# Amp.net
KiCad netlist of a schematic drawn in Altium Designer
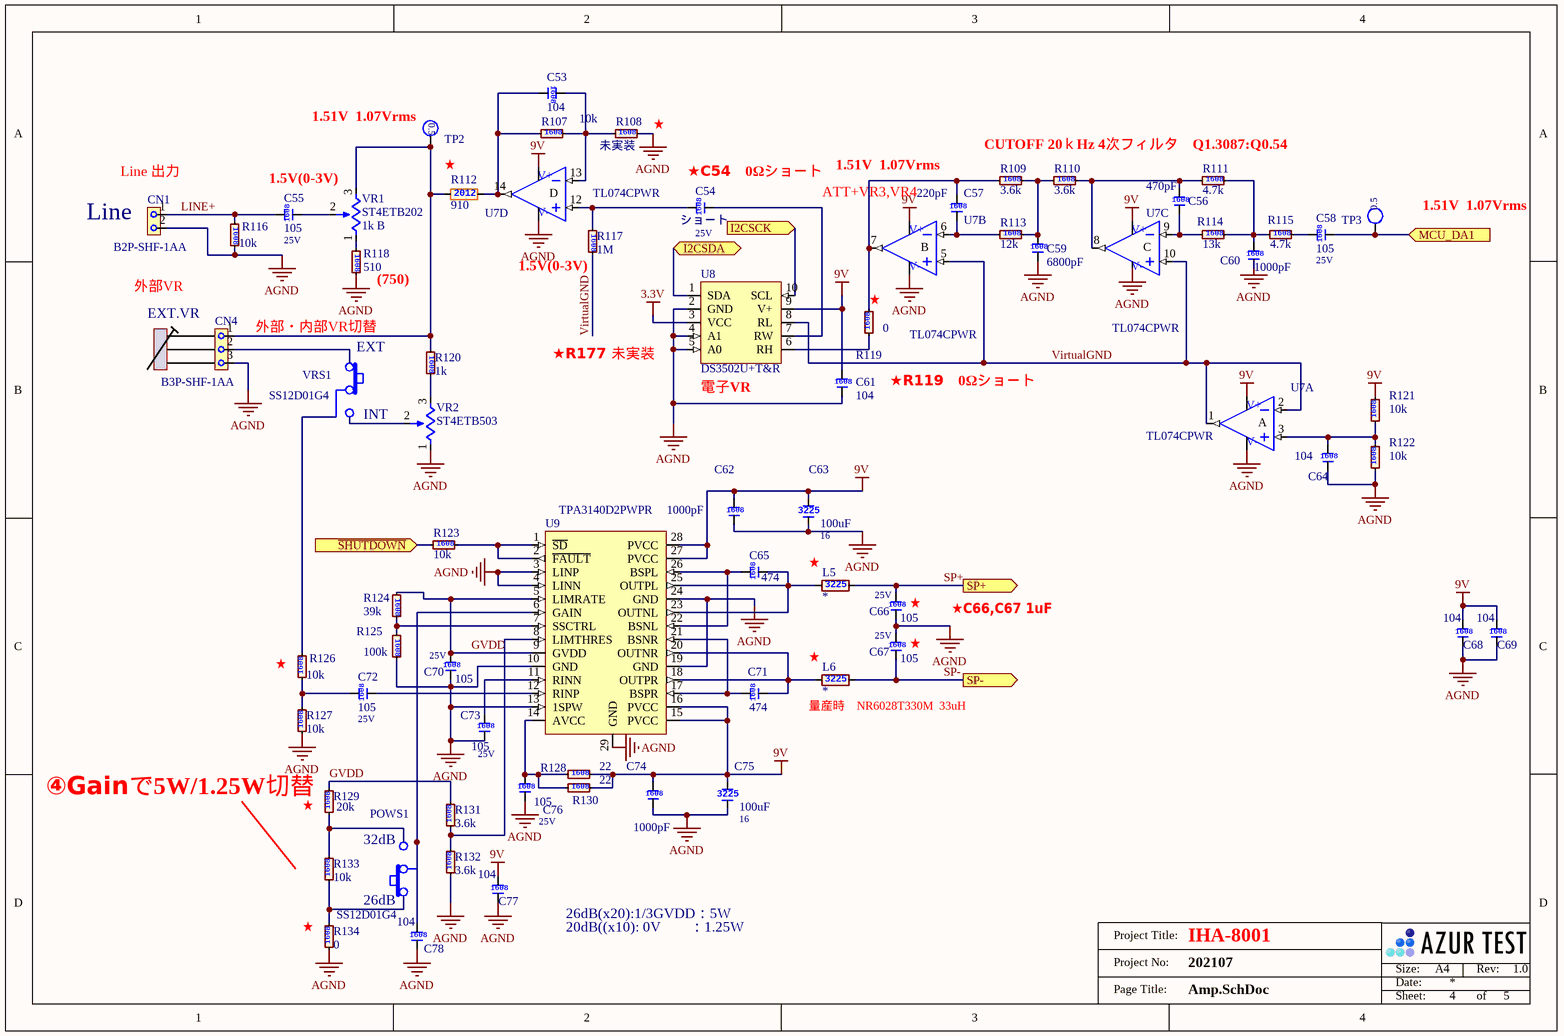
[diagram p0: Amp.SchDoc]

(export (version "E")
  (design (tool "Eeschema 10.0.6"))
  (components
    (comp (ref "C53")
      (value "CGA3E2X7R1H104K080AA")
      (footprint "C1608")
      (description "セラコン1608サイズ")
      (fields (field (name "TAG") "104") (field (name "VOLTAGE") "50V"))
      (libsource (lib "Audio") (part "C1608"))
    )
    (comp (ref "C54")
      (value "TMK107BJ105MA-T")
      (footprint "C1608")
      (description "セラコン1608サイズ")
      (fields (field (name "TAG") "ショート") (field (name "VOLTAGE") "25V"))
      (libsource (lib "Audio") (part "C1608"))
    )
    (comp (ref "C55")
      (value "TMK107BJ105MA-T")
      (footprint "C1608")
      (description "セラコン1608サイズ")
      (fields (field (name "TAG") "105") (field (name "VOLTAGE") "25V"))
      (libsource (lib "Audio") (part "C1608"))
    )
    (comp (ref "C56")
      (value "GCM1885C2A471JA16D")
      (footprint "C1608")
      (description "セラコン1608サイズ")
      (fields (field (name "TAG") "470pF") (field (name "VOLTAGE") "100V"))
      (libsource (lib "Audio") (part "C1608"))
    )
    (comp (ref "C57")
      (value "GCM1885C2A221JA16D")
      (footprint "C1608")
      (description "セラコン1608サイズ")
      (fields (field (name "TAG") "220pF") (field (name "VOLTAGE") "100V"))
      (libsource (lib "Audio") (part "C1608"))
    )
    (comp (ref "C58")
      (value "TMK107BJ105MA-T")
      (footprint "C1608")
      (description "セラコン1608サイズ")
      (fields (field (name "TAG") "105") (field (name "VOLTAGE") "25V"))
      (libsource (lib "Audio") (part "C1608"))
    )
    (comp (ref "C59")
      (value "GCM1885C2A682JA16D")
      (footprint "C1608")
      (description "セラコン1608サイズ")
      (fields (field (name "TAG") "6800pF") (field (name "VOLTAGE") "100V"))
      (libsource (lib "Audio") (part "C1608"))
    )
    (comp (ref "C60")
      (value "GCM1885C2A102JA16D")
      (footprint "C1608")
      (description "セラコン1608サイズ")
      (fields (field (name "TAG") "1000pF") (field (name "VOLTAGE") "100V"))
      (libsource (lib "Audio") (part "C1608"))
    )
    (comp (ref "C61")
      (value "CGA3E2X7R1H104K080AA")
      (footprint "C1608")
      (description "セラコン1608サイズ")
      (fields (field (name "TAG") "104") (field (name "VOLTAGE") "50V"))
      (libsource (lib "Audio") (part "C1608"))
    )
    (comp (ref "C62")
      (value "GCM1885C2A102JA16D")
      (footprint "C1608")
      (description "セラコン1608サイズ")
      (fields (field (name "TAG") "1000pF") (field (name "VOLTAGE") "100V"))
      (libsource (lib "Audio") (part "C1608"))
    )
    (comp (ref "C63")
      (value "EMK325ABJ107MM-T")
      (footprint "C3225")
      (description "セラコン3225サイズ")
      (fields (field (name "TAG") "100uF") (field (name "VOLTAGE") "16"))
      (libsource (lib "Audio") (part "C3225"))
    )
    (comp (ref "C64")
      (value "CGA3E2X7R1H104K080AA")
      (footprint "C1608")
      (description "セラコン1608サイズ")
      (fields (field (name "TAG") "104") (field (name "VOLTAGE") "50V"))
      (libsource (lib "Audio") (part "C1608"))
    )
    (comp (ref "C65")
      (value "UMK107B7474KA-TR")
      (footprint "C1608")
      (description "セラコン1608サイズ")
      (fields (field (name "TAG") "474") (field (name "VOLTAGE") "25V"))
      (libsource (lib "Audio") (part "C1608"))
    )
    (comp (ref "C66")
      (value "TMK107BJ105MA-T")
      (footprint "C1608")
      (description "セラコン1608サイズ")
      (fields (field (name "TAG") "105") (field (name "VOLTAGE") "25V"))
      (libsource (lib "Audio") (part "C1608"))
    )
    (comp (ref "C67")
      (value "TMK107BJ105MA-T")
      (footprint "C1608")
      (description "セラコン1608サイズ")
      (fields (field (name "TAG") "105") (field (name "VOLTAGE") "25V"))
      (libsource (lib "Audio") (part "C1608"))
    )
    (comp (ref "C68")
      (value "CGA3E2X7R1H104K080AA")
      (footprint "C1608")
      (description "セラコン1608サイズ")
      (fields (field (name "TAG") "104") (field (name "VOLTAGE") "50V"))
      (libsource (lib "Audio") (part "C1608"))
    )
    (comp (ref "C69")
      (value "CGA3E2X7R1H104K080AA")
      (footprint "C1608")
      (description "セラコン1608サイズ")
      (fields (field (name "TAG") "104") (field (name "VOLTAGE") "50V"))
      (libsource (lib "Audio") (part "C1608"))
    )
    (comp (ref "C70")
      (value "TMK107BJ105MA-T")
      (footprint "C1608")
      (description "セラコン1608サイズ")
      (fields (field (name "TAG") "105") (field (name "VOLTAGE") "25V"))
      (libsource (lib "Audio") (part "C1608"))
    )
    (comp (ref "C71")
      (value "UMK107B7474KA-TR")
      (footprint "C1608")
      (description "セラコン1608サイズ")
      (fields (field (name "TAG") "474") (field (name "VOLTAGE") "25V"))
      (libsource (lib "Audio") (part "C1608"))
    )
    (comp (ref "C72")
      (value "TMK107BJ105MA-T")
      (footprint "C1608")
      (description "セラコン1608サイズ")
      (fields (field (name "TAG") "105") (field (name "VOLTAGE") "25V"))
      (libsource (lib "Audio") (part "C1608"))
    )
    (comp (ref "C73")
      (value "TMK107BJ105MA-T")
      (footprint "C1608")
      (description "セラコン1608サイズ")
      (fields (field (name "TAG") "105") (field (name "VOLTAGE") "25V"))
      (libsource (lib "Audio") (part "C1608"))
    )
    (comp (ref "C74")
      (value "GCM1885C2A102JA16D")
      (footprint "C1608")
      (description "セラコン1608サイズ")
      (fields (field (name "TAG") "1000pF") (field (name "VOLTAGE") "100V"))
      (libsource (lib "Audio") (part "C1608"))
    )
    (comp (ref "C75")
      (value "EMK325ABJ107MM-T")
      (footprint "C3225")
      (description "セラコン3225サイズ")
      (fields (field (name "TAG") "100uF") (field (name "VOLTAGE") "16"))
      (libsource (lib "Audio") (part "C3225"))
    )
    (comp (ref "C76")
      (value "TMK107BJ105MA-T")
      (footprint "C1608")
      (description "セラコン1608サイズ")
      (fields (field (name "TAG") "105") (field (name "VOLTAGE") "25V"))
      (libsource (lib "Audio") (part "C1608"))
    )
    (comp (ref "C77")
      (value "CGA3E2X7R1H104K080AA")
      (footprint "C1608")
      (description "セラコン1608サイズ")
      (fields (field (name "TAG") "104") (field (name "VOLTAGE") "50V"))
      (libsource (lib "Audio") (part "C1608"))
    )
    (comp (ref "C78")
      (value "CGA3E2X7R1H104K080AA")
      (footprint "C1608")
      (description "セラコン1608サイズ")
      (fields (field (name "TAG") "104") (field (name "VOLTAGE") "50V"))
      (libsource (lib "Audio") (part "C1608"))
    )
    (comp (ref "CN1")
      (value "B2P-SHF-1AA")
      (footprint "B2P-SHF-1AA")
      (description "雄,ストレート,1列2ピン")
      (libsource (lib "Audio Prj_1") (part "B2P-SHF-1AA"))
    )
    (comp (ref "CN4")
      (value "B3P-SHF-1AA")
      (footprint "B3P-SHF-1AA")
      (description "雄,ストレート,1列3ピン")
      (libsource (lib "Audio") (part "B3P-SHF-1AA"))
    )
    (comp (ref "L5")
      (value "TF3225")
      (footprint "R3225")
      (description "厚膜チップ抵抗3225サイズ")
      (fields (field (name "TAG") "*"))
      (libsource (lib "Audio Prj") (part "TF3225"))
    )
    (comp (ref "L6")
      (value "TF3225")
      (footprint "R3225")
      (description "厚膜チップ抵抗3225サイズ")
      (fields (field (name "TAG") "*"))
      (libsource (lib "Audio Prj") (part "TF3225"))
    )
    (comp (ref "POWS1")
      (value "SS12D01G4")
      (footprint "SS12D01G4")
      (description "SPDTスライドスイッチ")
      (libsource (lib "Audio Prj") (part "SS12D01G4"))
    )
    (comp (ref "R107")
      (value "ERJ-PA3F1002V")
      (footprint "R1608")
      (description "厚膜チップ抵抗1608サイズ")
      (fields (field (name "TAG") "10k"))
      (libsource (lib "") (part "TF1608_1"))
    )
    (comp (ref "R108")
      (value "ERJ-PA3F1002V")
      (footprint "R1608")
      (description "厚膜チップ抵抗1608サイズ")
      (fields (field (name "TAG") "未実装"))
      (libsource (lib "") (part "TF1608_1"))
    )
    (comp (ref "R109")
      (value "ERJ-PA3F3601V")
      (footprint "R1608")
      (description "厚膜チップ抵抗1608サイズ")
      (fields (field (name "TAG") "3.6k"))
      (libsource (lib "") (part "TF1608_1"))
    )
    (comp (ref "R110")
      (value "ERJ-PA3F3601V")
      (footprint "R1608")
      (description "厚膜チップ抵抗1608サイズ")
      (fields (field (name "TAG") "3.6k"))
      (libsource (lib "") (part "TF1608_1"))
    )
    (comp (ref "R111")
      (value "ERJ-PA3F4701V")
      (footprint "R1608")
      (description "厚膜チップ抵抗1608サイズ")
      (fields (field (name "TAG") "4.7k"))
      (libsource (lib "") (part "TF1608_1"))
    )
    (comp (ref "R112")
      (value "ERJ-P08J911V")
      (footprint "R2012")
      (description "薄膜チップ抵抗2012サイズ")
      (fields (field (name "TAG") "910"))
      (libsource (lib "Audio") (part "MF2012"))
    )
    (comp (ref "R113")
      (value "ERJ-PA3F1201V")
      (footprint "R1608")
      (description "厚膜チップ抵抗1608サイズ")
      (fields (field (name "TAG") "12k"))
      (libsource (lib "") (part "TF1608_1"))
    )
    (comp (ref "R114")
      (value "ERJ-PA3F1302V")
      (footprint "R1608")
      (description "厚膜チップ抵抗1608サイズ")
      (fields (field (name "TAG") "13k"))
      (libsource (lib "") (part "TF1608_1"))
    )
    (comp (ref "R115")
      (value "ERJ-PA3F4701V")
      (footprint "R1608")
      (description "厚膜チップ抵抗1608サイズ")
      (fields (field (name "TAG") "4.7k"))
      (libsource (lib "") (part "TF1608_1"))
    )
    (comp (ref "R116")
      (value "ERJ-PA3F1002V")
      (footprint "R1608")
      (description "厚膜チップ抵抗1608サイズ")
      (fields (field (name "TAG") "10k"))
      (libsource (lib "Schlib1") (part "TF1608"))
    )
    (comp (ref "R117")
      (value "ERJ-PA3F1004V")
      (footprint "R1608")
      (description "厚膜チップ抵抗1608サイズ")
      (fields (field (name "TAG") "1M"))
      (libsource (lib "Schlib1") (part "TF1608"))
    )
    (comp (ref "R118")
      (value "ERJ-PA3F5100V")
      (footprint "R1608")
      (description "厚膜チップ抵抗1608サイズ")
      (fields (field (name "TAG") "510"))
      (libsource (lib "Schlib1") (part "TF1608"))
    )
    (comp (ref "R119")
      (value "ERJ-S030R00V")
      (footprint "R1608")
      (description "厚膜チップ抵抗1608サイズ")
      (fields (field (name "TAG") "0"))
      (libsource (lib "") (part "TF1608_2"))
    )
    (comp (ref "R120")
      (value "ERJ-PA3F1001V")
      (footprint "R1608")
      (description "厚膜チップ抵抗1608サイズ")
      (fields (field (name "TAG") "1k"))
      (libsource (lib "Schlib1") (part "TF1608"))
    )
    (comp (ref "R121")
      (value "ERJ-PA3F1002V")
      (footprint "R1608")
      (description "厚膜チップ抵抗1608サイズ")
      (fields (field (name "TAG") "10k"))
      (libsource (lib "") (part "TF1608_2"))
    )
    (comp (ref "R122")
      (value "ERJ-PA3F1002V")
      (footprint "R1608")
      (description "厚膜チップ抵抗1608サイズ")
      (fields (field (name "TAG") "10k"))
      (libsource (lib "") (part "TF1608_2"))
    )
    (comp (ref "R123")
      (value "ERJ-PA3F1002V")
      (footprint "R1608")
      (description "厚膜チップ抵抗1608サイズ")
      (fields (field (name "TAG") "10k"))
      (libsource (lib "") (part "TF1608_1"))
    )
    (comp (ref "R124")
      (value "ERJ-PA3F3902V")
      (footprint "R1608")
      (description "厚膜チップ抵抗1608サイズ")
      (fields (field (name "TAG") "39k"))
      (libsource (lib "Schlib1") (part "TF1608"))
    )
    (comp (ref "R125")
      (value "ERJ-PA3F3902V")
      (footprint "R1608")
      (description "厚膜チップ抵抗1608サイズ")
      (fields (field (name "TAG") "100k"))
      (libsource (lib "Schlib1") (part "TF1608"))
    )
    (comp (ref "R126")
      (value "ERJ-PA3F1002V")
      (footprint "R1608")
      (description "厚膜チップ抵抗1608サイズ")
      (fields (field (name "TAG") "10k"))
      (libsource (lib "") (part "TF1608_2"))
    )
    (comp (ref "R127")
      (value "ERJ-PA3F1002V")
      (footprint "R1608")
      (description "厚膜チップ抵抗1608サイズ")
      (fields (field (name "TAG") "10k"))
      (libsource (lib "") (part "TF1608_2"))
    )
    (comp (ref "R128")
      (value "ERJ-PA3F22R0V")
      (footprint "R1608")
      (description "厚膜チップ抵抗1608サイズ")
      (fields (field (name "TAG") "22"))
      (libsource (lib "") (part "TF1608_1"))
    )
    (comp (ref "R129")
      (value "ERJ-PA3F2002V")
      (footprint "R1608")
      (description "厚膜チップ抵抗1608サイズ")
      (fields (field (name "TAG") "20k"))
      (libsource (lib "") (part "TF1608_2"))
    )
    (comp (ref "R130")
      (value "ERJ-PA3F22R0V")
      (footprint "R1608")
      (description "厚膜チップ抵抗1608サイズ")
      (fields (field (name "TAG") "22"))
      (libsource (lib "") (part "TF1608_1"))
    )
    (comp (ref "R131")
      (value "ERJ-PA3F3601V")
      (footprint "R1608")
      (description "厚膜チップ抵抗1608サイズ")
      (fields (field (name "TAG") "3.6k"))
      (libsource (lib "") (part "TF1608_2"))
    )
    (comp (ref "R132")
      (value "ERJ-PA3F3601V")
      (footprint "R1608")
      (description "厚膜チップ抵抗1608サイズ")
      (fields (field (name "TAG") "3.6k"))
      (libsource (lib "") (part "TF1608_2"))
    )
    (comp (ref "R133")
      (value "ERJ-PA3F1002V")
      (footprint "R1608")
      (description "厚膜チップ抵抗1608サイズ")
      (fields (field (name "TAG") "10k"))
      (libsource (lib "") (part "TF1608_2"))
    )
    (comp (ref "R134")
      (value "ERJ-S030R00V")
      (footprint "R1608")
      (description "厚膜チップ抵抗1608サイズ")
      (fields (field (name "TAG") "0"))
      (libsource (lib "") (part "TF1608_2"))
    )
    (comp (ref "TP2")
      (value "TP0.5mm")
      (footprint "TP0.5mm")
      (description "Test-Point 0.5mm")
      (libsource (lib "Audio") (part "TP0.5mm"))
    )
    (comp (ref "TP3")
      (value "TP0.5mm")
      (footprint "TP0.5mm")
      (description "Test-Point 0.5mm")
      (libsource (lib "Audio") (part "TP0.5mm"))
    )
    (comp (ref "U7")
      (value "TL074CPWR")
      (footprint "TSSOP14")
      (description "IC OPAMP JFET 4 CIRCUIT 14TSSOP")
      (libsource (lib "Audio Prj") (part "TL084CPT"))
    )
    (comp (ref "U8")
      (value "DS3502U+T&R")
      (footprint "MSOP10")
      (description "IC DGTL POT 10KOHM 128TAP 10UMAX")
      (libsource (lib "Audio Prj") (part "DS3502U+T&R"))
    )
    (comp (ref "U9")
      (value "TPA3140D2PWPR")
      (footprint "TSSOP28")
      (description "IC AMP CLASS D STER 10W 28HTSSOP")
      (libsource (lib "Audio Prj") (part "TPA3140D2PWPR"))
    )
    (comp (ref "VR1")
      (value "ST4ETB202")
      (footprint "ST4ETB202")
      (description "CERMET TRIMMER  Top adjustmet")
      (fields (field (name "TAG") "1k B"))
      (libsource (lib "Audio") (part "ST-32EA**"))
    )
    (comp (ref "VR2")
      (value "ST4ETB503")
      (footprint "ST4ETB202")
      (description "CERMET TRIMMER  Top adjustmet")
      (libsource (lib "Audio") (part "ST-32EA**"))
    )
    (comp (ref "VRS1")
      (value "SS12D01G4")
      (footprint "SS12D01G4")
      (description "SPDTスライドスイッチ")
      (libsource (lib "Audio Prj") (part "SS12D01G4"))
    )
  )
  (nets
    (net (code "1") (name "/GVDD") (class "Default")
      (node (ref "C70") (pin "2") (pinfunction "2_2") (pintype "passive"))
      (node (ref "R124") (pin "1") (pinfunction "1_1") (pintype "passive"))
      (node (ref "R129") (pin "2") (pinfunction "2_2") (pintype "passive"))
      (node (ref "R131") (pin "2") (pinfunction "2_2") (pintype "passive"))
      (node (ref "U9") (pin "5") (pinfunction "LIMRATE_5") (pintype "input"))
      (node (ref "U9") (pin "9") (pinfunction "GVDD_9") (pintype "power_in"))
    )
    (net (code "2") (name "/I2CSCK") (class "Default")
      (node (ref "U8") (pin "10") (pinfunction "SCL_10") (pintype "input"))
    )
    (net (code "3") (name "/I2CSDA") (class "Default")
      (node (ref "U8") (pin "1") (pinfunction "SDA_1") (pintype "bidirectional"))
    )
    (net (code "4") (name "/LINE+") (class "Default")
      (node (ref "C55") (pin "2") (pinfunction "2_2") (pintype "passive"))
      (node (ref "CN1") (pin "1") (pinfunction "1_1") (pintype "passive"))
      (node (ref "R116") (pin "1") (pinfunction "1_1") (pintype "passive"))
    )
    (net (code "5") (name "/MCU_DA1") (class "Default")
      (node (ref "C58") (pin "1") (pinfunction "1_1") (pintype "passive"))
      (node (ref "TP3") (pin "1") (pinfunction "1_1") (pintype "passive"))
    )
    (net (code "6") (name "/SP+") (class "Default")
      (node (ref "C66") (pin "2") (pinfunction "2_2") (pintype "passive"))
      (node (ref "L5") (pin "2") (pinfunction "2_2") (pintype "passive"))
    )
    (net (code "7") (name "/SP-") (class "Default")
      (node (ref "C67") (pin "1") (pinfunction "1_1") (pintype "passive"))
      (node (ref "L6") (pin "2") (pinfunction "2_2") (pintype "passive"))
    )
    (net (code "8") (name "/VirtualGND") (class "Default")
      (node (ref "R117") (pin "2") (pinfunction "2_2") (pintype "passive"))
      (node (ref "U7") (pin "1") (pinfunction "OUT_1") (pintype "output"))
      (node (ref "U7") (pin "10") (pinfunction "IN+_10") (pintype "input"))
      (node (ref "U7") (pin "2") (pinfunction "IN-_2") (pintype "input"))
      (node (ref "U7") (pin "5") (pinfunction "IN+_5") (pintype "input"))
      (node (ref "U8") (pin "8") (pinfunction "RL_8") (pintype "passive"))
    )
    (net (code "9") (name "/~{SHUTDOWN}") (class "Default")
      (node (ref "R123") (pin "1") (pinfunction "1_1") (pintype "passive"))
    )
    (net (code "10") (name "3.3V") (class "Default")
      (node (ref "U8") (pin "3") (pinfunction "VCC_3") (pintype "power_in"))
    )
    (net (code "11") (name "9V") (class "Default")
      (node (ref "C61") (pin "2") (pinfunction "2_2") (pintype "passive"))
      (node (ref "C62") (pin "2") (pinfunction "2_2") (pintype "passive"))
      (node (ref "C63") (pin "2") (pinfunction "2_2") (pintype "passive"))
      (node (ref "C68") (pin "2") (pinfunction "2_2") (pintype "passive"))
      (node (ref "C69") (pin "2") (pinfunction "2_2") (pintype "passive"))
      (node (ref "C74") (pin "2") (pinfunction "2_2") (pintype "passive"))
      (node (ref "C75") (pin "2") (pinfunction "2_2") (pintype "passive"))
      (node (ref "C77") (pin "2") (pinfunction "2_2") (pintype "passive"))
      (node (ref "R121") (pin "2") (pinfunction "2_2") (pintype "passive"))
      (node (ref "R128") (pin "2") (pinfunction "2_2") (pintype "passive"))
      (node (ref "R130") (pin "2") (pinfunction "2_2") (pintype "passive"))
      (node (ref "U7") (pin "4") (pinfunction "V+_4") (pintype "power_in"))
      (node (ref "U8") (pin "9") (pinfunction "V+_9") (pintype "power_in"))
      (node (ref "U9") (pin "15") (pinfunction "PVCC_15") (pintype "power_in"))
      (node (ref "U9") (pin "16") (pinfunction "PVCC_16") (pintype "power_in"))
      (node (ref "U9") (pin "27") (pinfunction "PVCC_27") (pintype "power_in"))
      (node (ref "U9") (pin "28") (pinfunction "PVCC_28") (pintype "power_in"))
    )
    (net (code "12") (name "AGND") (class "Default")
      (node (ref "C59") (pin "1") (pinfunction "1_1") (pintype "passive"))
      (node (ref "C60") (pin "1") (pinfunction "1_1") (pintype "passive"))
      (node (ref "C61") (pin "1") (pinfunction "1_1") (pintype "passive"))
      (node (ref "C62") (pin "1") (pinfunction "1_1") (pintype "passive"))
      (node (ref "C63") (pin "1") (pinfunction "1_1") (pintype "passive"))
      (node (ref "C64") (pin "1") (pinfunction "1_1") (pintype "passive"))
      (node (ref "C66") (pin "1") (pinfunction "1_1") (pintype "passive"))
      (node (ref "C67") (pin "2") (pinfunction "2_2") (pintype "passive"))
      (node (ref "C68") (pin "1") (pinfunction "1_1") (pintype "passive"))
      (node (ref "C69") (pin "1") (pinfunction "1_1") (pintype "passive"))
      (node (ref "C70") (pin "1") (pinfunction "1_1") (pintype "passive"))
      (node (ref "C73") (pin "1") (pinfunction "1_1") (pintype "passive"))
      (node (ref "C74") (pin "1") (pinfunction "1_1") (pintype "passive"))
      (node (ref "C75") (pin "1") (pinfunction "1_1") (pintype "passive"))
      (node (ref "C76") (pin "1") (pinfunction "1_1") (pintype "passive"))
      (node (ref "C77") (pin "1") (pinfunction "1_1") (pintype "passive"))
      (node (ref "C78") (pin "1") (pinfunction "1_1") (pintype "passive"))
      (node (ref "CN1") (pin "2") (pinfunction "2_2") (pintype "passive"))
      (node (ref "CN4") (pin "3") (pinfunction "3_3") (pintype "passive"))
      (node (ref "R108") (pin "2") (pinfunction "2_2") (pintype "passive"))
      (node (ref "R116") (pin "2") (pinfunction "2_2") (pintype "passive"))
      (node (ref "R118") (pin "2") (pinfunction "2_2") (pintype "passive"))
      (node (ref "R122") (pin "1") (pinfunction "1_1") (pintype "passive"))
      (node (ref "R125") (pin "2") (pinfunction "2_2") (pintype "passive"))
      (node (ref "R127") (pin "1") (pinfunction "1_1") (pintype "passive"))
      (node (ref "R132") (pin "1") (pinfunction "1_1") (pintype "passive"))
      (node (ref "R134") (pin "1") (pinfunction "1_1") (pintype "passive"))
      (node (ref "U7") (pin "11") (pinfunction "V-_11") (pintype "power_in"))
      (node (ref "U8") (pin "2") (pinfunction "GND_2") (pintype "power_in"))
      (node (ref "U8") (pin "4") (pinfunction "A1_4") (pintype "input"))
      (node (ref "U8") (pin "5") (pinfunction "A0_5") (pintype "input"))
      (node (ref "U9") (pin "10") (pinfunction "GND_10") (pintype "power_in"))
      (node (ref "U9") (pin "13") (pinfunction "1SPW_13") (pintype "input"))
      (node (ref "U9") (pin "19") (pinfunction "GND_19") (pintype "power_in"))
      (node (ref "U9") (pin "24") (pinfunction "GND_24") (pintype "power_in"))
      (node (ref "U9") (pin "29") (pinfunction "GND_29") (pintype "power_in"))
      (node (ref "U9") (pin "3") (pinfunction "LINP_3") (pintype "input"))
      (node (ref "U9") (pin "4") (pinfunction "LINN_4") (pintype "input"))
      (node (ref "VR2") (pin "1") (pinfunction "1_1") (pintype "passive"))
    )
    (net (code "13") (name "Net-(C55-Pad1)") (class "Default")
      (node (ref "C55") (pin "1") (pinfunction "1_1") (pintype "passive"))
      (node (ref "VR1") (pin "2") (pinfunction "2_2") (pintype "passive"))
    )
    (net (code "14") (name "Net-(C58-Pad2)") (class "Default")
      (node (ref "C58") (pin "2") (pinfunction "2_2") (pintype "passive"))
      (node (ref "R115") (pin "2") (pinfunction "2_2") (pintype "passive"))
    )
    (net (code "15") (name "Net-(C59-Pad2)") (class "Default")
      (node (ref "C59") (pin "2") (pinfunction "2_2") (pintype "passive"))
      (node (ref "R109") (pin "2") (pinfunction "2_2") (pintype "passive"))
      (node (ref "R110") (pin "1") (pinfunction "1_1") (pintype "passive"))
      (node (ref "R113") (pin "2") (pinfunction "2_2") (pintype "passive"))
    )
    (net (code "16") (name "Net-(C60-Pad2)") (class "Default")
      (node (ref "C60") (pin "2") (pinfunction "2_2") (pintype "passive"))
      (node (ref "R111") (pin "2") (pinfunction "2_2") (pintype "passive"))
      (node (ref "R114") (pin "2") (pinfunction "2_2") (pintype "passive"))
      (node (ref "R115") (pin "1") (pinfunction "1_1") (pintype "passive"))
    )
    (net (code "17") (name "Net-(C72-Pad2)") (class "Default")
      (node (ref "C72") (pin "2") (pinfunction "2_2") (pintype "passive"))
      (node (ref "R126") (pin "1") (pinfunction "1_1") (pintype "passive"))
      (node (ref "R127") (pin "2") (pinfunction "2_2") (pintype "passive"))
    )
    (net (code "18") (name "Net-(CN4-Pad1)") (class "Default")
      (node (ref "CN4") (pin "1") (pinfunction "1_1") (pintype "passive"))
      (node (ref "R112") (pin "1") (pinfunction "1_1") (pintype "passive"))
      (node (ref "R120") (pin "1") (pinfunction "1_1") (pintype "passive"))
      (node (ref "TP2") (pin "1") (pinfunction "1_1") (pintype "passive"))
      (node (ref "VR1") (pin "3") (pinfunction "3_3") (pintype "passive"))
    )
    (net (code "19") (name "Net-(CN4-Pad2)") (class "Default")
      (node (ref "CN4") (pin "2") (pinfunction "2_2") (pintype "passive"))
      (node (ref "VRS1") (pin "1") (pinfunction "1_1") (pintype "passive"))
    )
    (net (code "20") (name "Net-(POWS1-Pad1)") (class "Default")
      (node (ref "POWS1") (pin "1") (pinfunction "1_1") (pintype "passive"))
      (node (ref "R133") (pin "1") (pinfunction "1_1") (pintype "passive"))
      (node (ref "R134") (pin "2") (pinfunction "2_2") (pintype "passive"))
    )
    (net (code "21") (name "Net-(POWS1-Pad3)") (class "Default")
      (node (ref "POWS1") (pin "3") (pinfunction "3_3") (pintype "passive"))
      (node (ref "R129") (pin "1") (pinfunction "1_1") (pintype "passive"))
      (node (ref "R133") (pin "2") (pinfunction "2_2") (pintype "passive"))
    )
    (net (code "22") (name "Net-(R118-Pad1)") (class "Default")
      (node (ref "R118") (pin "1") (pinfunction "1_1") (pintype "passive"))
      (node (ref "VR1") (pin "1") (pinfunction "1_1") (pintype "passive"))
    )
    (net (code "23") (name "Net-(R120-Pad2)") (class "Default")
      (node (ref "R120") (pin "2") (pinfunction "2_2") (pintype "passive"))
      (node (ref "VR2") (pin "3") (pinfunction "3_3") (pintype "passive"))
    )
    (net (code "24") (name "Net-(R126-Pad2)") (class "Default")
      (node (ref "R126") (pin "2") (pinfunction "2_2") (pintype "passive"))
      (node (ref "VRS1") (pin "2") (pinfunction "2_2") (pintype "passive"))
    )
    (net (code "25") (name "Net-(U7A-IN+)") (class "Default")
      (node (ref "C64") (pin "2") (pinfunction "2_2") (pintype "passive"))
      (node (ref "R121") (pin "1") (pinfunction "1_1") (pintype "passive"))
      (node (ref "R122") (pin "2") (pinfunction "2_2") (pintype "passive"))
      (node (ref "U7") (pin "3") (pinfunction "IN+_3") (pintype "input"))
    )
    (net (code "26") (name "Net-(U7B-IN-)") (class "Default")
      (node (ref "C57") (pin "1") (pinfunction "1_1") (pintype "passive"))
      (node (ref "R113") (pin "1") (pinfunction "1_1") (pintype "passive"))
      (node (ref "U7") (pin "6") (pinfunction "IN-_6") (pintype "input"))
    )
    (net (code "27") (name "Net-(U7B-OUT)") (class "Default")
      (node (ref "C57") (pin "2") (pinfunction "2_2") (pintype "passive"))
      (node (ref "R109") (pin "1") (pinfunction "1_1") (pintype "passive"))
      (node (ref "R119") (pin "2") (pinfunction "2_2") (pintype "passive"))
      (node (ref "U7") (pin "7") (pinfunction "OUT_7") (pintype "output"))
    )
    (net (code "28") (name "Net-(U7C-IN-)") (class "Default")
      (node (ref "C56") (pin "1") (pinfunction "1_1") (pintype "passive"))
      (node (ref "R114") (pin "1") (pinfunction "1_1") (pintype "passive"))
      (node (ref "U7") (pin "9") (pinfunction "IN-_9") (pintype "input"))
    )
    (net (code "29") (name "Net-(U7C-OUT)") (class "Default")
      (node (ref "C56") (pin "2") (pinfunction "2_2") (pintype "passive"))
      (node (ref "R110") (pin "2") (pinfunction "2_2") (pintype "passive"))
      (node (ref "R111") (pin "1") (pinfunction "1_1") (pintype "passive"))
      (node (ref "U7") (pin "8") (pinfunction "OUT_8") (pintype "output"))
    )
    (net (code "30") (name "Net-(U7D-IN+)") (class "Default")
      (node (ref "C54") (pin "2") (pinfunction "2_2") (pintype "passive"))
      (node (ref "R117") (pin "1") (pinfunction "1_1") (pintype "passive"))
      (node (ref "U7") (pin "12") (pinfunction "IN+_12") (pintype "input"))
    )
    (net (code "31") (name "Net-(U7D-IN-)") (class "Default")
      (node (ref "C53") (pin "2") (pinfunction "2_2") (pintype "passive"))
      (node (ref "R107") (pin "2") (pinfunction "2_2") (pintype "passive"))
      (node (ref "R108") (pin "1") (pinfunction "1_1") (pintype "passive"))
      (node (ref "U7") (pin "13") (pinfunction "IN-_13") (pintype "input"))
    )
    (net (code "32") (name "Net-(U7D-OUT)") (class "Default")
      (node (ref "C53") (pin "1") (pinfunction "1_1") (pintype "passive"))
      (node (ref "R107") (pin "1") (pinfunction "1_1") (pintype "passive"))
      (node (ref "R112") (pin "2") (pinfunction "2_2") (pintype "passive"))
      (node (ref "U7") (pin "14") (pinfunction "OUT_14") (pintype "output"))
    )
    (net (code "33") (name "Net-(U8-RH)") (class "Default")
      (node (ref "R119") (pin "1") (pinfunction "1_1") (pintype "passive"))
      (node (ref "U8") (pin "6") (pinfunction "RH_6") (pintype "passive"))
    )
    (net (code "34") (name "Net-(U8-RW)") (class "Default")
      (node (ref "C54") (pin "1") (pinfunction "1_1") (pintype "passive"))
      (node (ref "U8") (pin "7") (pinfunction "RW_7") (pintype "passive"))
    )
    (net (code "35") (name "Net-(U9-AVCC)") (class "Default")
      (node (ref "C76") (pin "2") (pinfunction "2_2") (pintype "passive"))
      (node (ref "R128") (pin "1") (pinfunction "1_1") (pintype "passive"))
      (node (ref "R130") (pin "1") (pinfunction "1_1") (pintype "passive"))
      (node (ref "U9") (pin "14") (pinfunction "AVCC_14") (pintype "power_in"))
    )
    (net (code "36") (name "Net-(U9-BSNL)") (class "Default")
      (node (ref "C65") (pin "2") (pinfunction "2_2") (pintype "passive"))
      (node (ref "U9") (pin "22") (pinfunction "BSNL_22") (pintype "input"))
      (node (ref "U9") (pin "26") (pinfunction "BSPL_26") (pintype "input"))
    )
    (net (code "37") (name "Net-(U9-BSNR)") (class "Default")
      (node (ref "C71") (pin "2") (pinfunction "2_2") (pintype "passive"))
      (node (ref "U9") (pin "17") (pinfunction "BSPR_17") (pintype "input"))
      (node (ref "U9") (pin "21") (pinfunction "BSNR_21") (pintype "input"))
    )
    (net (code "38") (name "Net-(U9-GAIN)") (class "Default")
      (node (ref "C78") (pin "2") (pinfunction "2_2") (pintype "passive"))
      (node (ref "POWS1") (pin "2") (pinfunction "2_2") (pintype "passive"))
      (node (ref "U9") (pin "6") (pinfunction "GAIN_6") (pintype "input"))
    )
    (net (code "39") (name "Net-(U9-LIMTHRES)") (class "Default")
      (node (ref "R131") (pin "1") (pinfunction "1_1") (pintype "passive"))
      (node (ref "R132") (pin "2") (pinfunction "2_2") (pintype "passive"))
      (node (ref "U9") (pin "8") (pinfunction "LIMTHRES_8") (pintype "input"))
    )
    (net (code "40") (name "Net-(U9-OUTNL)") (class "Default")
      (node (ref "C65") (pin "1") (pinfunction "1_1") (pintype "passive"))
      (node (ref "L5") (pin "1") (pinfunction "1_1") (pintype "passive"))
      (node (ref "U9") (pin "23") (pinfunction "OUTNL_23") (pintype "output"))
      (node (ref "U9") (pin "25") (pinfunction "OUTPL_25") (pintype "output"))
    )
    (net (code "41") (name "Net-(U9-OUTNR)") (class "Default")
      (node (ref "C71") (pin "1") (pinfunction "1_1") (pintype "passive"))
      (node (ref "L6") (pin "1") (pinfunction "1_1") (pintype "passive"))
      (node (ref "U9") (pin "18") (pinfunction "OUTPR_18") (pintype "output"))
      (node (ref "U9") (pin "20") (pinfunction "OUTNR_20") (pintype "output"))
    )
    (net (code "42") (name "Net-(U9-RINN)") (class "Default")
      (node (ref "C73") (pin "2") (pinfunction "2_2") (pintype "passive"))
      (node (ref "U9") (pin "11") (pinfunction "RINN_11") (pintype "input"))
    )
    (net (code "43") (name "Net-(U9-RINP)") (class "Default")
      (node (ref "C72") (pin "1") (pinfunction "1_1") (pintype "passive"))
      (node (ref "U9") (pin "12") (pinfunction "RINP_12") (pintype "input"))
    )
    (net (code "44") (name "Net-(U9-SSCTRL)") (class "Default")
      (node (ref "R124") (pin "2") (pinfunction "2_2") (pintype "passive"))
      (node (ref "R125") (pin "1") (pinfunction "1_1") (pintype "passive"))
      (node (ref "U9") (pin "7") (pinfunction "SSCTRL_7") (pintype "input"))
    )
    (net (code "45") (name "Net-(U9-~{FAULT})") (class "Default")
      (node (ref "R123") (pin "2") (pinfunction "2_2") (pintype "passive"))
      (node (ref "U9") (pin "1") (pinfunction "~{SD}_1") (pintype "input"))
      (node (ref "U9") (pin "2") (pinfunction "~{FAULT}_2") (pintype "output"))
    )
    (net (code "46") (name "Net-(VR2-Pad2)") (class "Default")
      (node (ref "VR2") (pin "2") (pinfunction "2_2") (pintype "passive"))
      (node (ref "VRS1") (pin "3") (pinfunction "3_3") (pintype "passive"))
    )
    (net (code "47") (name "unconnected-(U7C-V--Pad11)") (class "Default")
      (node (ref "U7") (pin "11") (pinfunction "V-_11") (pintype "power_in"))
    )
  )
)
